# 07_PCIE_WIFI.net
KiCad netlist of a schematic drawn in Altium Designer
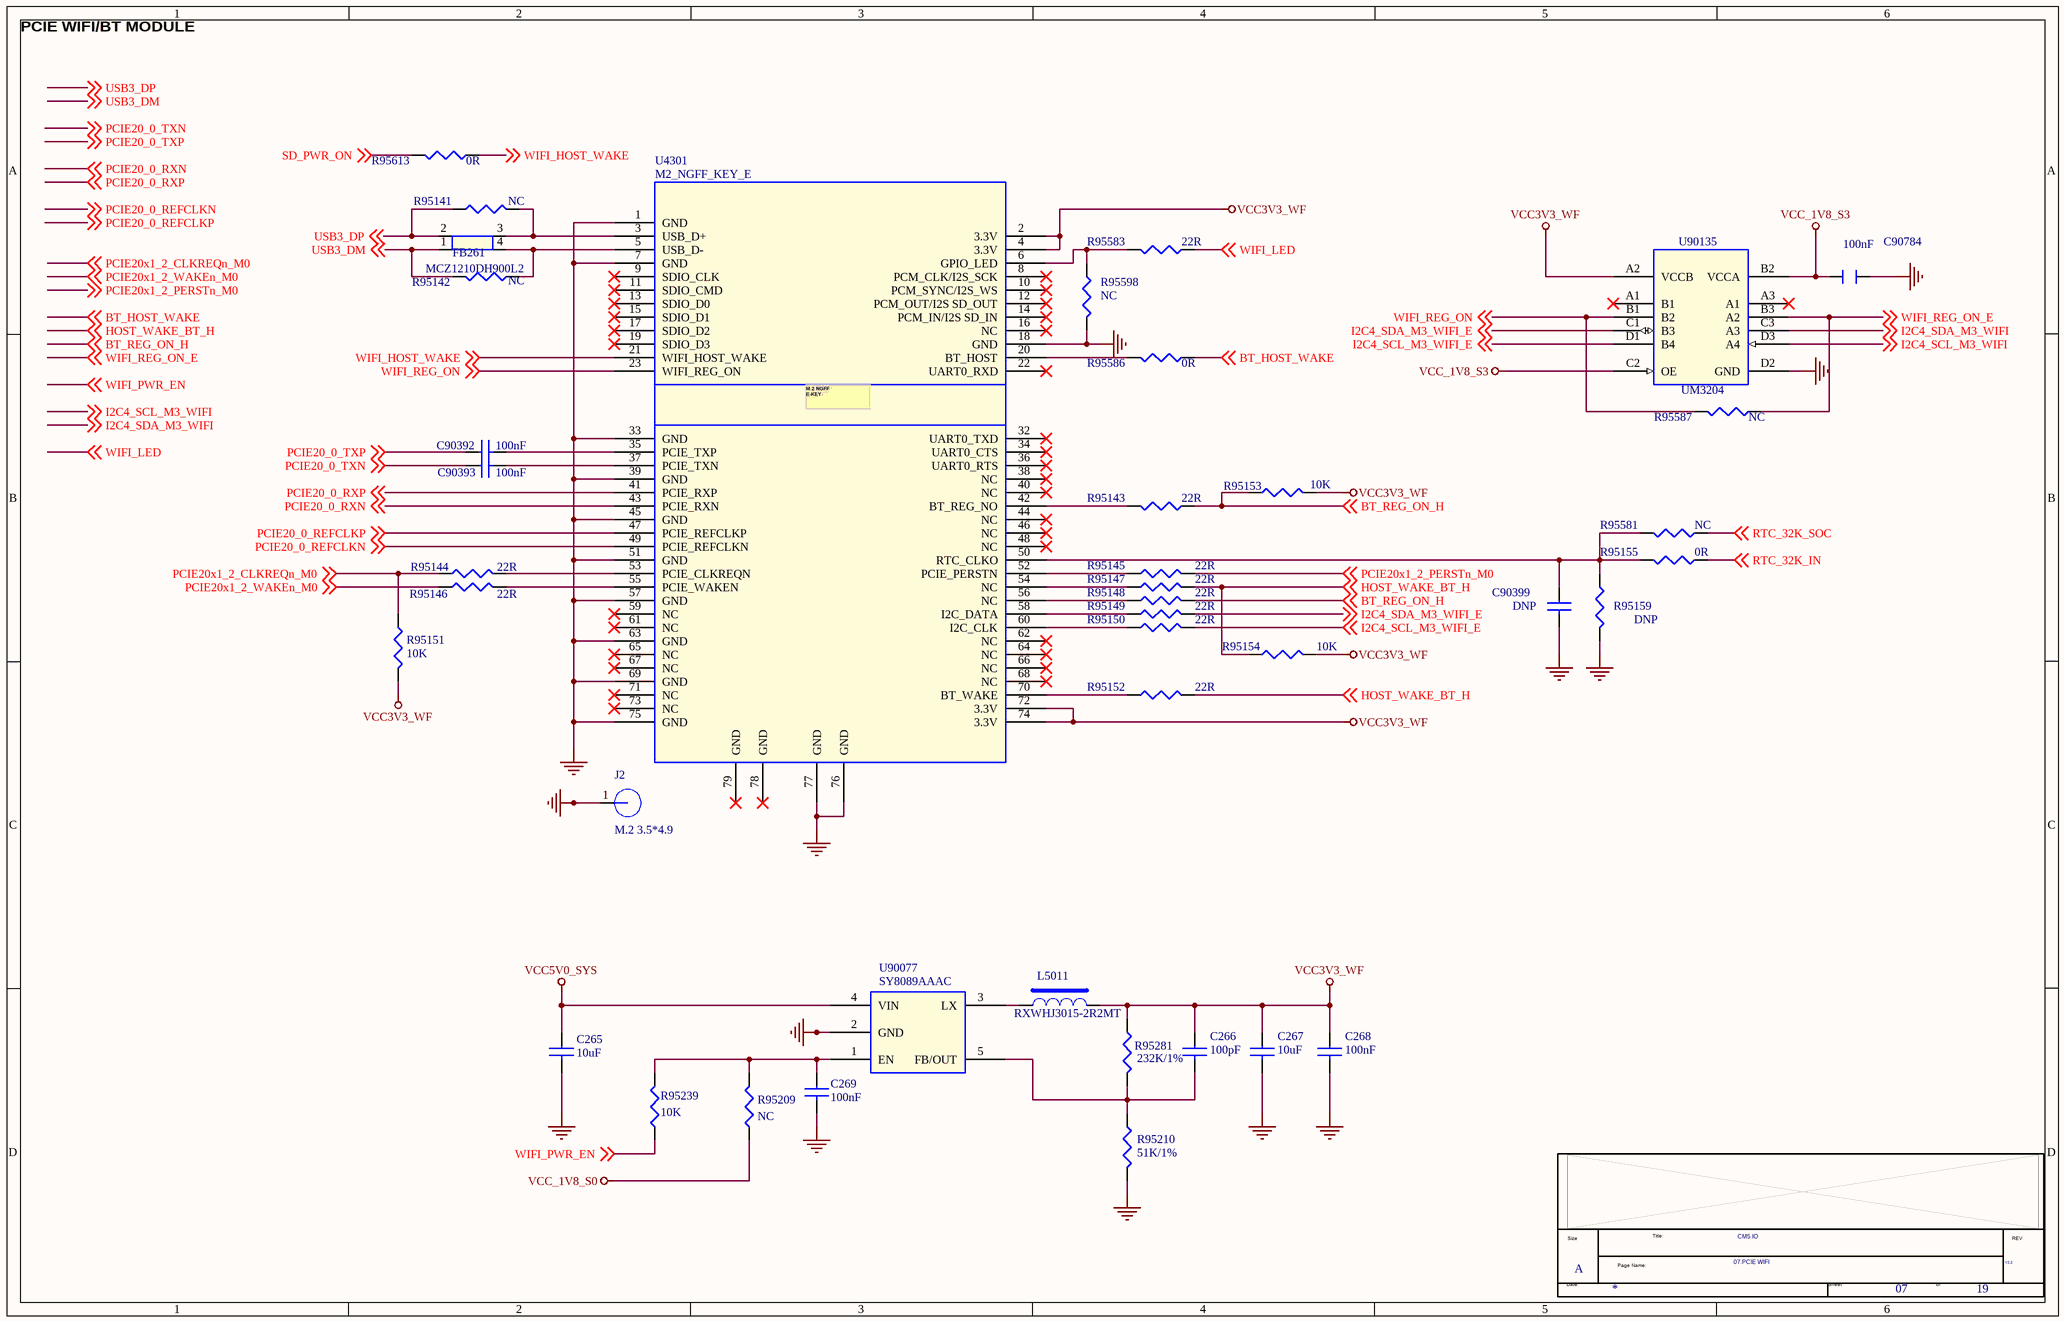
[diagram p0: 07_PCIE_WIFI.SchDoc]

(export (version "E")
  (design (tool "Eeschema 10.0.6"))
  (components
    (comp (ref "*")
      (value "radxa_1010")
      (fields
        (field (name "DOC") "07.PCIE WIFI")
        (field (name "REVCODE") "V2.2")
        (field (name "TITLE") "CM5 IO")
        (field (name "PAGE SIZE") "A")
        (field (name "PAGE NUMBER") "07")
        (field (name "PAGE COUNT") "19")
      )
      (libsource (lib "*") (part "radxa_1010"))
    )
    (comp (ref "C265")
      (value "10uF")
      (footprint "C0603")
      (description "cap,10.00uF,+/-10%,10V,X5R,C0805")
      (fields
        (field (name "VOLTAGE") "6.3V")
        (field (name "TOLERANCE") "10%")
        (field (name "CREATED BY") "JJJ")
      )
      (libsource (lib "*") (part "CAP NP_0_Dup5"))
    )
    (comp (ref "C266")
      (value "100pF")
      (footprint "C0201")
      (description "cap,100.00pF,+/-5%,50V,C0G,C0402")
      (fields
        (field (name "VOLTAGE") "25V")
        (field (name "TOLERANCE") "5%")
        (field (name "CREATED BY") "JJJ")
      )
      (libsource (lib "*") (part "CAP NP_0_Dup5"))
    )
    (comp (ref "C267")
      (value "10uF")
      (footprint "C0603")
      (description "cap,10.00uF,+/-10%,10V,X5R,C0805")
      (fields
        (field (name "VOLTAGE") "6.3V")
        (field (name "TOLERANCE") "10%")
        (field (name "CREATED BY") "JJJ")
      )
      (libsource (lib "*") (part "CAP NP_0_Dup5"))
    )
    (comp (ref "C268")
      (value "100nF")
      (footprint "C0201")
      (description "cap,100.00nF,+/-10%,16V,X5R,C0402")
      (fields
        (field (name "VOLTAGE") "16V")
        (field (name "TOLERANCE") "10%")
        (field (name "CREATED BY") "JJJ")
      )
      (libsource (lib "*") (part "CAP NP_0_Dup5"))
    )
    (comp (ref "C269")
      (value "100nF")
      (footprint "C0201")
      (description "cap,100.00nF,+/-10%,16V,X5R,C0402")
      (fields
        (field (name "VOLTAGE") "16V")
        (field (name "MANUFACTURER") "TDK")
        (field (name "CREATED BY") "JJJ")
      )
      (libsource (lib "*") (part "CAP NP_0_Dup5"))
    )
    (comp (ref "C90392")
      (value "100nF")
      (footprint "C0201")
      (description "cap,100.00nF,+/-10%,10V,X5R,C0201")
      (fields
        (field (name "VOLTAGE") "10V")
        (field (name "TOLERANCE") "10%")
        (field (name "CREATED BY") "JJJ")
      )
      (libsource (lib "*") (part "CAP NP_0_Dup5"))
    )
    (comp (ref "C90393")
      (value "100nF")
      (footprint "C0201")
      (description "cap,100.00nF,+/-10%,10V,X5R,C0201")
      (fields
        (field (name "VOLTAGE") "10V")
        (field (name "MANUFACTURER") "TDK")
        (field (name "CREATED BY") "JJJ")
      )
      (libsource (lib "*") (part "CAP NP_0_Dup5"))
    )
    (comp (ref "C90399")
      (value "DNP")
      (footprint "C0402")
      (description "Did Not Place.")
      (fields (field (name "CREATED BY") "JJJ"))
      (libsource (lib "*") (part "CAP NP_0_Dup5"))
    )
    (comp (ref "C90784") (value "100nF") (footprint "C0402") (libsource (lib "*") (part "CAPACITOR_0")))
    (comp (ref "FB261")
      (value "MCZ1210DH900L2")
      (footprint "MCZ1210AH900L2")
      (libsource (lib "*") (part "MCZ1210AH900L2_1_Dup1"))
    )
    (comp (ref "J2")
      (value "M.2 3.5*4.9")
      (footprint "H3.8MM")
      (description "直径3.5mm hole")
      (fields (field (name "CREATED BY") "CZD"))
      (libsource (lib "*") (part "HOLE"))
    )
    (comp (ref "L5011")
      (value "RXWHJ3015-2R2MT")
      (footprint "IND_303015")
      (description "Power Inductor,2.2uH,0.3,IND_303015")
      (fields
        (field (name "MANUFACTURER") "sunlord")
        (field (name "TOLERANCE") "30%")
        (field (name "CREATED BY") "YTL")
      )
      (libsource (lib "*") (part "INDUCTORS OF FERRITE_Dup1"))
    )
    (comp (ref "R95141")
      (value "NC")
      (footprint "R0402")
      (description "通用厚膜电阻,33R,+/-5%,R0402,1/16W.")
      (fields
        (field (name "TOLERANCE") "5%")
        (field (name "MANUFACTURER") "YAGEO")
        (field (name "CREATED BY") "YTL")
      )
      (libsource (lib "*") (part "RESISTOR_0_Dup2"))
    )
    (comp (ref "R95142")
      (value "NC")
      (footprint "R0402")
      (description "通用厚膜电阻,33R,+/-5%,R0402,1/16W.")
      (fields
        (field (name "TOLERANCE") "5%")
        (field (name "MANUFACTURER") "YAGEO")
        (field (name "CREATED BY") "YTL")
      )
      (libsource (lib "*") (part "RESISTOR_0_Dup2"))
    )
    (comp (ref "R95143")
      (value "22R")
      (footprint "R0402")
      (description "通用厚膜电阻,22R,+/-5%,R0402,1/16W.")
      (fields
        (field (name "TOLERANCE") "5%")
        (field (name "MANUFACTURER") "YAGEO")
        (field (name "CREATED BY") "YTL")
      )
      (libsource (lib "*") (part "RESISTOR_0_Dup2"))
    )
    (comp (ref "R95144")
      (value "22R")
      (footprint "R0402")
      (description "通用厚膜电阻,22R,+/-5%,R0402,1/16W.")
      (fields
        (field (name "TOLERANCE") "5%")
        (field (name "MANUFACTURER") "YAGEO")
        (field (name "CREATED BY") "YTL")
      )
      (libsource (lib "*") (part "RESISTOR_0_Dup2"))
    )
    (comp (ref "R95145")
      (value "22R")
      (footprint "R0402")
      (description "通用厚膜电阻,22R,+/-5%,R0402,1/16W.")
      (fields
        (field (name "TOLERANCE") "5%")
        (field (name "MANUFACTURER") "YAGEO")
        (field (name "CREATED BY") "YTL")
      )
      (libsource (lib "*") (part "RESISTOR_0_Dup2"))
    )
    (comp (ref "R95146")
      (value "22R")
      (footprint "R0402")
      (description "通用厚膜电阻,22R,+/-5%,R0402,1/16W.")
      (fields
        (field (name "TOLERANCE") "5%")
        (field (name "MANUFACTURER") "YAGEO")
        (field (name "CREATED BY") "YTL")
      )
      (libsource (lib "*") (part "RESISTOR_0_Dup2"))
    )
    (comp (ref "R95147")
      (value "22R")
      (footprint "R0402")
      (description "通用厚膜电阻,22R,+/-5%,R0402,1/16W.")
      (fields
        (field (name "TOLERANCE") "5%")
        (field (name "MANUFACTURER") "YAGEO")
        (field (name "CREATED BY") "YTL")
      )
      (libsource (lib "*") (part "RESISTOR_0_Dup2"))
    )
    (comp (ref "R95148")
      (value "22R")
      (footprint "R0402")
      (description "通用厚膜电阻,22R,+/-5%,R0402,1/16W.")
      (fields
        (field (name "TOLERANCE") "5%")
        (field (name "MANUFACTURER") "YAGEO")
        (field (name "CREATED BY") "YTL")
      )
      (libsource (lib "*") (part "RESISTOR_0_Dup2"))
    )
    (comp (ref "R95149")
      (value "22R")
      (footprint "R0402")
      (description "通用厚膜电阻,22R,+/-5%,R0402,1/16W.")
      (fields
        (field (name "TOLERANCE") "5%")
        (field (name "MANUFACTURER") "YAGEO")
        (field (name "CREATED BY") "YTL")
      )
      (libsource (lib "*") (part "RESISTOR_0_Dup2"))
    )
    (comp (ref "R95150")
      (value "22R")
      (footprint "R0402")
      (description "通用厚膜电阻,22R,+/-5%,R0402,1/16W.")
      (fields
        (field (name "TOLERANCE") "5%")
        (field (name "MANUFACTURER") "YAGEO")
        (field (name "CREATED BY") "YTL")
      )
      (libsource (lib "*") (part "RESISTOR_0_Dup2"))
    )
    (comp (ref "R95151")
      (value "10K")
      (footprint "R0402")
      (description "通用厚膜电阻,10K,+/-5%,R0402,1/16W.")
      (fields
        (field (name "TOLERANCE") "5%")
        (field (name "MANUFACTURER") "YAGEO")
        (field (name "CREATED BY") "YTL")
      )
      (libsource (lib "*") (part "RESISTOR_0_Dup2"))
    )
    (comp (ref "R95152")
      (value "22R")
      (footprint "R0402")
      (description "通用厚膜电阻,22R,+/-5%,R0402,1/16W.")
      (fields
        (field (name "TOLERANCE") "5%")
        (field (name "MANUFACTURER") "YAGEO")
        (field (name "CREATED BY") "YTL")
      )
      (libsource (lib "*") (part "RESISTOR_0_Dup2"))
    )
    (comp (ref "R95153")
      (value "10K")
      (footprint "R0402")
      (description "通用厚膜电阻,10K,+/-5%,R0402,1/16W.")
      (fields
        (field (name "TOLERANCE") "5%")
        (field (name "MANUFACTURER") "YAGEO")
        (field (name "CREATED BY") "YTL")
      )
      (libsource (lib "*") (part "RESISTOR_0_Dup2"))
    )
    (comp (ref "R95154")
      (value "10K")
      (footprint "R0402")
      (description "通用厚膜电阻,10K,+/-5%,R0402,1/16W.")
      (fields
        (field (name "TOLERANCE") "5%")
        (field (name "MANUFACTURER") "YAGEO")
        (field (name "CREATED BY") "YTL")
      )
      (libsource (lib "*") (part "RESISTOR_0_Dup2"))
    )
    (comp (ref "R95155")
      (value "0R")
      (footprint "R0402")
      (description "通用厚膜电阻,0R,+/-5%,R0402,1/16W.")
      (fields
        (field (name "TOLERANCE") "5%")
        (field (name "MANUFACTURER") "YAGEO")
        (field (name "CREATED BY") "YTL")
      )
      (libsource (lib "*") (part "RESISTOR_0_Dup2"))
    )
    (comp (ref "R95159")
      (value "DNP")
      (footprint "R0402")
      (description "Did Not Place.")
      (fields (field (name "CREATED BY") "JJJ"))
      (libsource (lib "*") (part "RESISTOR_0_Dup2"))
    )
    (comp (ref "R95209")
      (value "NC")
      (footprint "R0402")
      (description "通用厚膜电阻,10K,+/-5%,R0402,1/16W.")
      (fields
        (field (name "TOLERANCE") "5%")
        (field (name "MANUFACTURER") "YAGEO")
        (field (name "CREATED BY") "YTL")
      )
      (libsource (lib "*") (part "RESISTOR_0_Dup2"))
    )
    (comp (ref "R95210")
      (value "51K/1%")
      (footprint "R0402")
      (description "通用厚膜电阻,47K,+/-1%,R0402,1/16W.")
      (fields
        (field (name "TOLERANCE") "1%")
        (field (name "MANUFACTURER") "YAGEO")
        (field (name "CREATED BY") "YTL")
      )
      (libsource (lib "*") (part "RESISTOR_0_Dup2"))
    )
    (comp (ref "R95239")
      (value "10K")
      (footprint "R0402")
      (description "通用厚膜电阻,10K,+/-5%,R0402,1/16W.")
      (fields
        (field (name "TOLERANCE") "5%")
        (field (name "MANUFACTURER") "YAGEO")
        (field (name "CREATED BY") "YTL")
      )
      (libsource (lib "*") (part "RESISTOR_0_Dup2"))
    )
    (comp (ref "R95281")
      (value "232K/1%")
      (footprint "R0402")
      (description "通用厚膜电阻,200K,+/-1%,R0402,1/16W.")
      (fields
        (field (name "TOLERANCE") "1%")
        (field (name "MANUFACTURER") "YAGEO")
        (field (name "CREATED BY") "YTL")
      )
      (libsource (lib "*") (part "RESISTOR_0_Dup2"))
    )
    (comp (ref "R95581")
      (value "NC")
      (footprint "R0402")
      (description "通用厚膜电阻,0R,+/-5%,R0402,1/16W.")
      (fields
        (field (name "TOLERANCE") "5%")
        (field (name "MANUFACTURER") "YAGEO")
        (field (name "CREATED BY") "YTL")
      )
      (libsource (lib "*") (part "RESISTOR_0_Dup2"))
    )
    (comp (ref "R95583")
      (value "22R")
      (footprint "R0402")
      (description "通用厚膜电阻,22R,+/-5%,R0402,1/16W.")
      (fields
        (field (name "TOLERANCE") "5%")
        (field (name "MANUFACTURER") "YAGEO")
        (field (name "CREATED BY") "YTL")
      )
      (libsource (lib "*") (part "RESISTOR_0_Dup2"))
    )
    (comp (ref "R95586")
      (value "0R")
      (footprint "R0402")
      (description "通用厚膜电阻,22R,+/-5%,R0402,1/16W.")
      (fields
        (field (name "TOLERANCE") "5%")
        (field (name "MANUFACTURER") "YAGEO")
        (field (name "CREATED BY") "YTL")
      )
      (libsource (lib "*") (part "RESISTOR_0_Dup2"))
    )
    (comp (ref "R95587")
      (value "NC")
      (footprint "R0402")
      (description "通用厚膜电阻,22R,+/-5%,R0402,1/16W.")
      (fields
        (field (name "TOLERANCE") "5%")
        (field (name "MANUFACTURER") "YAGEO")
        (field (name "CREATED BY") "YTL")
      )
      (libsource (lib "*") (part "RESISTOR_0_Dup2"))
    )
    (comp (ref "R95598")
      (value "NC")
      (footprint "R0402")
      (description "通用厚膜电阻,22R,+/-5%,R0402,1/16W.")
      (fields
        (field (name "TOLERANCE") "5%")
        (field (name "MANUFACTURER") "YAGEO")
        (field (name "CREATED BY") "YTL")
      )
      (libsource (lib "*") (part "RESISTOR_0_Dup2"))
    )
    (comp (ref "R95613")
      (value "0R")
      (footprint "R0402")
      (description "通用厚膜电阻,22R,+/-5%,R0402,1/16W.")
      (fields
        (field (name "TOLERANCE") "5%")
        (field (name "MANUFACTURER") "YAGEO")
        (field (name "CREATED BY") "YTL")
      )
      (libsource (lib "*") (part "RESISTOR_0_Dup2"))
    )
    (comp (ref "U4301")
      (value "M2_NGFF_KEY_E")
      (footprint "M2_NGFF_KEY_E_1")
      (libsource (lib "*") (part "M_8.2 NGFF EKEY SOCKET"))
    )
    (comp (ref "U90077")
      (value "SY8089AAAC")
      (footprint "SOT_23_5")
      (description "High Efficiency 5.5V, 2A continuous, 3A peak, 1MHz Synchronous Step Down Regulator")
      (fields (field (name "MANUFACTURER") "Silergy（矽力杰）") (field (name "CREATED BY") "JJJ"))
      (libsource (lib "*") (part "DCDC_SY8088"))
    )
    (comp (ref "U90135")
      (value "UM3204")
      (footprint "CSP-12")
      (description "4-bit Bi-directional Level Shifter  UM3204H")
      (fields (field (name "PART NUMBER") "PI4ULS5V104GAEX"))
      (libsource (lib "*") (part "MP2610_0"))
    )
  )
  (nets
    (net (code "1") (name "BT_HOST_WAKE") (class "Default")
      (node (ref "R95586") (pin "1") (pinfunction "1_1") (pintype "passive"))
    )
    (net (code "2") (name "BT_REG_ON_H") (class "Default")
      (node (ref "R95143") (pin "1") (pinfunction "1_1") (pintype "passive"))
      (node (ref "R95148") (pin "1") (pinfunction "1_1") (pintype "passive"))
      (node (ref "R95153") (pin "1") (pinfunction "1_1") (pintype "passive"))
    )
    (net (code "3") (name "GND") (class "Default")
      (node (ref "C265") (pin "2") (pinfunction "2_2") (pintype "passive"))
      (node (ref "C267") (pin "2") (pinfunction "2_2") (pintype "passive"))
      (node (ref "C268") (pin "2") (pinfunction "2_2") (pintype "passive"))
      (node (ref "C269") (pin "2") (pinfunction "2_2") (pintype "passive"))
      (node (ref "C90399") (pin "2") (pinfunction "2_2") (pintype "passive"))
      (node (ref "C90784") (pin "1") (pinfunction "1_1") (pintype "passive"))
      (node (ref "J2") (pin "1") (pinfunction "1_1") (pintype "passive"))
      (node (ref "R95159") (pin "2") (pinfunction "2_2") (pintype "passive"))
      (node (ref "R95210") (pin "2") (pinfunction "2_2") (pintype "passive"))
      (node (ref "R95598") (pin "2") (pinfunction "2_2") (pintype "passive"))
      (node (ref "U4301") (pin "1") (pinfunction "GND_1") (pintype "passive"))
      (node (ref "U4301") (pin "18") (pinfunction "GND_18") (pintype "passive"))
      (node (ref "U4301") (pin "33") (pinfunction "GND_33") (pintype "passive"))
      (node (ref "U4301") (pin "39") (pinfunction "GND_39") (pintype "passive"))
      (node (ref "U4301") (pin "45") (pinfunction "GND_45") (pintype "passive"))
      (node (ref "U4301") (pin "51") (pinfunction "GND_51") (pintype "passive"))
      (node (ref "U4301") (pin "57") (pinfunction "GND_57") (pintype "passive"))
      (node (ref "U4301") (pin "63") (pinfunction "GND_63") (pintype "passive"))
      (node (ref "U4301") (pin "69") (pinfunction "GND_69") (pintype "passive"))
      (node (ref "U4301") (pin "7") (pinfunction "GND_7") (pintype "passive"))
      (node (ref "U4301") (pin "75") (pinfunction "GND_75") (pintype "passive"))
      (node (ref "U4301") (pin "76") (pinfunction "GND_76") (pintype "passive"))
      (node (ref "U4301") (pin "77") (pinfunction "GND_77") (pintype "passive"))
      (node (ref "U90077") (pin "2") (pinfunction "GND_2") (pintype "passive"))
      (node (ref "U90135") (pin "D2") (pinfunction "GND_D2") (pintype "power_in"))
    )
    (net (code "4") (name "HOST_WAKE_BT_H") (class "Default")
      (node (ref "R95147") (pin "1") (pinfunction "1_1") (pintype "passive"))
      (node (ref "R95152") (pin "1") (pinfunction "1_1") (pintype "passive"))
      (node (ref "R95154") (pin "1") (pinfunction "1_1") (pintype "passive"))
    )
    (net (code "5") (name "I2C4_SCL_M3_WIFI") (class "Default")
      (node (ref "U90135") (pin "D3") (pinfunction "A4_D3") (pintype "input"))
    )
    (net (code "6") (name "I2C4_SCL_M3_WIFI_E") (class "Default")
      (node (ref "R95150") (pin "1") (pinfunction "1_1") (pintype "passive"))
      (node (ref "U90135") (pin "D1") (pinfunction "B4_D1") (pintype "tri_state"))
    )
    (net (code "7") (name "I2C4_SDA_M3_WIFI") (class "Default")
      (node (ref "U90135") (pin "C3") (pinfunction "A3_C3") (pintype "tri_state"))
    )
    (net (code "8") (name "I2C4_SDA_M3_WIFI_E") (class "Default")
      (node (ref "R95149") (pin "1") (pinfunction "1_1") (pintype "passive"))
      (node (ref "U90135") (pin "C1") (pinfunction "B3_C1") (pintype "bidirectional"))
    )
    (net (code "9") (name "Net-(R95147-Pad2)") (class "Default")
      (node (ref "R95147") (pin "2") (pinfunction "2_2") (pintype "passive"))
      (node (ref "U4301") (pin "54") (pinfunction "NC_54") (pintype "passive"))
    )
    (net (code "10") (name "Net-(R95148-Pad2)") (class "Default")
      (node (ref "R95148") (pin "2") (pinfunction "2_2") (pintype "passive"))
      (node (ref "U4301") (pin "56") (pinfunction "NC_56") (pintype "passive"))
    )
    (net (code "11") (name "Net-(U4301-BT_HOST)") (class "Default")
      (node (ref "R95586") (pin "2") (pinfunction "2_2") (pintype "passive"))
      (node (ref "U4301") (pin "20") (pinfunction "BT_HOST_20") (pintype "passive"))
    )
    (net (code "12") (name "Net-(U4301-BT_REG_NO)") (class "Default")
      (node (ref "R95143") (pin "2") (pinfunction "2_2") (pintype "passive"))
      (node (ref "U4301") (pin "42") (pinfunction "BT_REG_NO_42") (pintype "passive"))
    )
    (net (code "13") (name "Net-(U4301-BT_WAKE)") (class "Default")
      (node (ref "R95152") (pin "2") (pinfunction "2_2") (pintype "passive"))
      (node (ref "U4301") (pin "70") (pinfunction "BT_WAKE_70") (pintype "passive"))
    )
    (net (code "14") (name "Net-(U4301-GPIO_LED)") (class "Default")
      (node (ref "R95583") (pin "2") (pinfunction "2_2") (pintype "passive"))
      (node (ref "R95598") (pin "1") (pinfunction "1_1") (pintype "passive"))
      (node (ref "U4301") (pin "6") (pinfunction "GPIO_LED_6") (pintype "passive"))
    )
    (net (code "15") (name "Net-(U4301-I2C_CLK)") (class "Default")
      (node (ref "R95150") (pin "2") (pinfunction "2_2") (pintype "passive"))
      (node (ref "U4301") (pin "60") (pinfunction "I2C_CLK_60") (pintype "passive"))
    )
    (net (code "16") (name "Net-(U4301-I2C_DATA)") (class "Default")
      (node (ref "R95149") (pin "2") (pinfunction "2_2") (pintype "passive"))
      (node (ref "U4301") (pin "58") (pinfunction "I2C_DATA_58") (pintype "passive"))
    )
    (net (code "17") (name "Net-(U4301-PCIE_CLKREQN)") (class "Default")
      (node (ref "R95144") (pin "2") (pinfunction "2_2") (pintype "passive"))
      (node (ref "U4301") (pin "53") (pinfunction "PCIE_CLKREQN_53") (pintype "passive"))
    )
    (net (code "18") (name "Net-(U4301-PCIE_PERSTN)") (class "Default")
      (node (ref "R95145") (pin "2") (pinfunction "2_2") (pintype "passive"))
      (node (ref "U4301") (pin "52") (pinfunction "PCIE_PERSTN_52") (pintype "passive"))
    )
    (net (code "19") (name "Net-(U4301-PCIE_TXN)") (class "Default")
      (node (ref "C90393") (pin "2") (pinfunction "2_2") (pintype "passive"))
      (node (ref "U4301") (pin "37") (pinfunction "PCIE_TXN_37") (pintype "passive"))
    )
    (net (code "20") (name "Net-(U4301-PCIE_TXP)") (class "Default")
      (node (ref "C90392") (pin "2") (pinfunction "2_2") (pintype "passive"))
      (node (ref "U4301") (pin "35") (pinfunction "PCIE_TXP_35") (pintype "passive"))
    )
    (net (code "21") (name "Net-(U4301-PCIE_WAKEN)") (class "Default")
      (node (ref "R95146") (pin "2") (pinfunction "2_2") (pintype "passive"))
      (node (ref "U4301") (pin "55") (pinfunction "PCIE_WAKEN_55") (pintype "passive"))
    )
    (net (code "22") (name "Net-(U4301-RTC_CLKO)") (class "Default")
      (node (ref "C90399") (pin "1") (pinfunction "1_1") (pintype "passive"))
      (node (ref "R95155") (pin "2") (pinfunction "2_2") (pintype "passive"))
      (node (ref "R95159") (pin "1") (pinfunction "1_1") (pintype "passive"))
      (node (ref "R95581") (pin "2") (pinfunction "2_2") (pintype "passive"))
      (node (ref "U4301") (pin "50") (pinfunction "RTC_CLKO_50") (pintype "passive"))
    )
    (net (code "23") (name "Net-(U4301-USB_D+)") (class "Default")
      (node (ref "FB261") (pin "3") (pinfunction "3_3") (pintype "passive"))
      (node (ref "R95141") (pin "1") (pinfunction "1_1") (pintype "passive"))
      (node (ref "U4301") (pin "3") (pinfunction "USB_D+_3") (pintype "passive"))
    )
    (net (code "24") (name "Net-(U4301-USB_D-)") (class "Default")
      (node (ref "FB261") (pin "4") (pinfunction "4_4") (pintype "passive"))
      (node (ref "R95142") (pin "1") (pinfunction "1_1") (pintype "passive"))
      (node (ref "U4301") (pin "5") (pinfunction "USB_D-_5") (pintype "passive"))
    )
    (net (code "25") (name "Net-(U90077-EN)") (class "Default")
      (node (ref "C269") (pin "1") (pinfunction "1_1") (pintype "passive"))
      (node (ref "R95209") (pin "2") (pinfunction "2_2") (pintype "passive"))
      (node (ref "R95239") (pin "2") (pinfunction "2_2") (pintype "passive"))
      (node (ref "U90077") (pin "1") (pinfunction "EN_1") (pintype "passive"))
    )
    (net (code "26") (name "Net-(U90077-FB{slash}OUT)") (class "Default")
      (node (ref "C266") (pin "2") (pinfunction "2_2") (pintype "passive"))
      (node (ref "R95210") (pin "1") (pinfunction "1_1") (pintype "passive"))
      (node (ref "R95281") (pin "2") (pinfunction "2_2") (pintype "passive"))
      (node (ref "U90077") (pin "5") (pinfunction "FB/OUT_5") (pintype "passive"))
    )
    (net (code "27") (name "Net-(U90077-LX)") (class "Default")
      (node (ref "L5011") (pin "1") (pinfunction "1_1") (pintype "passive"))
      (node (ref "U90077") (pin "3") (pinfunction "LX_3") (pintype "passive"))
    )
    (net (code "28") (name "PCIE20_0_REFCLKN") (class "Default")
      (node (ref "U4301") (pin "49") (pinfunction "PCIE_REFCLKN_49") (pintype "passive"))
    )
    (net (code "29") (name "PCIE20_0_REFCLKP") (class "Default")
      (node (ref "U4301") (pin "47") (pinfunction "PCIE_REFCLKP_47") (pintype "passive"))
    )
    (net (code "30") (name "PCIE20_0_RXN") (class "Default")
      (node (ref "U4301") (pin "43") (pinfunction "PCIE_RXN_43") (pintype "passive"))
    )
    (net (code "31") (name "PCIE20_0_RXP") (class "Default")
      (node (ref "U4301") (pin "41") (pinfunction "PCIE_RXP_41") (pintype "passive"))
    )
    (net (code "32") (name "PCIE20_0_TXN") (class "Default")
      (node (ref "C90393") (pin "1") (pinfunction "1_1") (pintype "passive"))
    )
    (net (code "33") (name "PCIE20_0_TXP") (class "Default")
      (node (ref "C90392") (pin "1") (pinfunction "1_1") (pintype "passive"))
    )
    (net (code "34") (name "PCIE20x1_2_CLKREQn_M0") (class "Default")
      (node (ref "R95144") (pin "1") (pinfunction "1_1") (pintype "passive"))
      (node (ref "R95151") (pin "1") (pinfunction "1_1") (pintype "passive"))
    )
    (net (code "35") (name "PCIE20x1_2_PERSTn_M0") (class "Default")
      (node (ref "R95145") (pin "1") (pinfunction "1_1") (pintype "passive"))
    )
    (net (code "36") (name "PCIE20x1_2_WAKEn_M0") (class "Default")
      (node (ref "R95146") (pin "1") (pinfunction "1_1") (pintype "passive"))
    )
    (net (code "37") (name "RTC_32K_IN") (class "Default")
      (node (ref "R95155") (pin "1") (pinfunction "1_1") (pintype "passive"))
    )
    (net (code "38") (name "RTC_32K_SOC") (class "Default")
      (node (ref "R95581") (pin "1") (pinfunction "1_1") (pintype "passive"))
    )
    (net (code "39") (name "SD_PWR_ON") (class "Default")
      (node (ref "R95613") (pin "2") (pinfunction "2_2") (pintype "passive"))
    )
    (net (code "40") (name "USB3_DM") (class "Default")
      (node (ref "FB261") (pin "1") (pinfunction "1_1") (pintype "passive"))
      (node (ref "R95142") (pin "2") (pinfunction "2_2") (pintype "passive"))
    )
    (net (code "41") (name "USB3_DP") (class "Default")
      (node (ref "FB261") (pin "2") (pinfunction "2_2") (pintype "passive"))
      (node (ref "R95141") (pin "2") (pinfunction "2_2") (pintype "passive"))
    )
    (net (code "42") (name "VCC3V3_WF") (class "Default")
      (node (ref "C266") (pin "1") (pinfunction "1_1") (pintype "passive"))
      (node (ref "C267") (pin "1") (pinfunction "1_1") (pintype "passive"))
      (node (ref "C268") (pin "1") (pinfunction "1_1") (pintype "passive"))
      (node (ref "L5011") (pin "2") (pinfunction "2_2") (pintype "passive"))
      (node (ref "R95151") (pin "2") (pinfunction "2_2") (pintype "passive"))
      (node (ref "R95153") (pin "2") (pinfunction "2_2") (pintype "passive"))
      (node (ref "R95154") (pin "2") (pinfunction "2_2") (pintype "passive"))
      (node (ref "R95281") (pin "1") (pinfunction "1_1") (pintype "passive"))
      (node (ref "U4301") (pin "2") (pinfunction "3.3V_2") (pintype "passive"))
      (node (ref "U4301") (pin "4") (pinfunction "3.3V_4") (pintype "passive"))
      (node (ref "U4301") (pin "72") (pinfunction "3.3V_72") (pintype "passive"))
      (node (ref "U4301") (pin "74") (pinfunction "3.3V_74") (pintype "passive"))
      (node (ref "U90135") (pin "A2") (pinfunction "VCCB_A2") (pintype "power_in"))
    )
    (net (code "43") (name "VCC5V0_SYS") (class "Default")
      (node (ref "C265") (pin "1") (pinfunction "1_1") (pintype "passive"))
      (node (ref "U90077") (pin "4") (pinfunction "VIN_4") (pintype "passive"))
    )
    (net (code "44") (name "VCC_1V8_S0") (class "Default")
      (node (ref "R95209") (pin "1") (pinfunction "1_1") (pintype "passive"))
    )
    (net (code "45") (name "VCC_1V8_S3") (class "Default")
      (node (ref "C90784") (pin "2") (pinfunction "2_2") (pintype "passive"))
      (node (ref "U90135") (pin "B2") (pinfunction "VCCA_B2") (pintype "power_in"))
      (node (ref "U90135") (pin "C2") (pinfunction "OE_C2") (pintype "input"))
    )
    (net (code "46") (name "WIFI_HOST_WAKE") (class "Default")
      (node (ref "R95613") (pin "1") (pinfunction "1_1") (pintype "passive"))
      (node (ref "U4301") (pin "21") (pinfunction "WIFI_HOST_WAKE_21") (pintype "passive"))
    )
    (net (code "47") (name "WIFI_LED") (class "Default")
      (node (ref "R95583") (pin "1") (pinfunction "1_1") (pintype "passive"))
    )
    (net (code "48") (name "WIFI_PWR_EN") (class "Default")
      (node (ref "R95239") (pin "1") (pinfunction "1_1") (pintype "passive"))
    )
    (net (code "49") (name "WIFI_REG_ON") (class "Default")
      (node (ref "R95587") (pin "2") (pinfunction "2_2") (pintype "passive"))
      (node (ref "U4301") (pin "23") (pinfunction "WIFI_REG_ON_23") (pintype "passive"))
      (node (ref "U90135") (pin "B1") (pinfunction "B2_B1") (pintype "tri_state"))
    )
    (net (code "50") (name "WIFI_REG_ON_E") (class "Default")
      (node (ref "R95587") (pin "1") (pinfunction "1_1") (pintype "passive"))
      (node (ref "U90135") (pin "B3") (pinfunction "A2_B3") (pintype "tri_state"))
    )
    (net (code "51") (name "unconnected-(U4301-GND-Pad78)") (class "Default")
      (node (ref "U4301") (pin "78") (pinfunction "GND_78") (pintype "passive+no_connect"))
    )
    (net (code "52") (name "unconnected-(U4301-GND-Pad79)") (class "Default")
      (node (ref "U4301") (pin "79") (pinfunction "GND_79") (pintype "passive+no_connect"))
    )
    (net (code "53") (name "unconnected-(U4301-NC-Pad16)") (class "Default")
      (node (ref "U4301") (pin "16") (pinfunction "NC_16") (pintype "passive+no_connect"))
    )
    (net (code "54") (name "unconnected-(U4301-NC-Pad38)") (class "Default")
      (node (ref "U4301") (pin "38") (pinfunction "NC_38") (pintype "passive+no_connect"))
    )
    (net (code "55") (name "unconnected-(U4301-NC-Pad40)") (class "Default")
      (node (ref "U4301") (pin "40") (pinfunction "NC_40") (pintype "passive+no_connect"))
    )
    (net (code "56") (name "unconnected-(U4301-NC-Pad44)") (class "Default")
      (node (ref "U4301") (pin "44") (pinfunction "NC_44") (pintype "passive+no_connect"))
    )
    (net (code "57") (name "unconnected-(U4301-NC-Pad46)") (class "Default")
      (node (ref "U4301") (pin "46") (pinfunction "NC_46") (pintype "passive+no_connect"))
    )
    (net (code "58") (name "unconnected-(U4301-NC-Pad48)") (class "Default")
      (node (ref "U4301") (pin "48") (pinfunction "NC_48") (pintype "passive+no_connect"))
    )
    (net (code "59") (name "unconnected-(U4301-NC-Pad59)") (class "Default")
      (node (ref "U4301") (pin "59") (pinfunction "NC_59") (pintype "passive+no_connect"))
    )
    (net (code "60") (name "unconnected-(U4301-NC-Pad61)") (class "Default")
      (node (ref "U4301") (pin "61") (pinfunction "NC_61") (pintype "passive+no_connect"))
    )
    (net (code "61") (name "unconnected-(U4301-NC-Pad62)") (class "Default")
      (node (ref "U4301") (pin "62") (pinfunction "NC_62") (pintype "passive+no_connect"))
    )
    (net (code "62") (name "unconnected-(U4301-NC-Pad64)") (class "Default")
      (node (ref "U4301") (pin "64") (pinfunction "NC_64") (pintype "passive+no_connect"))
    )
    (net (code "63") (name "unconnected-(U4301-NC-Pad65)") (class "Default")
      (node (ref "U4301") (pin "65") (pinfunction "NC_65") (pintype "passive+no_connect"))
    )
    (net (code "64") (name "unconnected-(U4301-NC-Pad66)") (class "Default")
      (node (ref "U4301") (pin "66") (pinfunction "NC_66") (pintype "passive+no_connect"))
    )
    (net (code "65") (name "unconnected-(U4301-NC-Pad67)") (class "Default")
      (node (ref "U4301") (pin "67") (pinfunction "NC_67") (pintype "passive+no_connect"))
    )
    (net (code "66") (name "unconnected-(U4301-NC-Pad68)") (class "Default")
      (node (ref "U4301") (pin "68") (pinfunction "NC_68") (pintype "passive+no_connect"))
    )
    (net (code "67") (name "unconnected-(U4301-NC-Pad71)") (class "Default")
      (node (ref "U4301") (pin "71") (pinfunction "NC_71") (pintype "passive+no_connect"))
    )
    (net (code "68") (name "unconnected-(U4301-NC-Pad73)") (class "Default")
      (node (ref "U4301") (pin "73") (pinfunction "NC_73") (pintype "passive+no_connect"))
    )
    (net (code "69") (name "unconnected-(U4301-PCM_CLK{slash}I2S_SCK-Pad8)") (class "Default")
      (node (ref "U4301") (pin "8") (pinfunction "PCM_CLK/I2S_SCK_8") (pintype "passive+no_connect"))
    )
    (net (code "70") (name "unconnected-(U4301-PCM_IN{slash}I2S_SD_IN-Pad14)") (class "Default")
      (node (ref "U4301") (pin "14") (pinfunction "PCM_IN/I2S_SD_IN_14") (pintype "passive+no_connect"))
    )
    (net (code "71") (name "unconnected-(U4301-PCM_OUT{slash}I2S_SD_OUT-Pad12)") (class "Default")
      (node (ref "U4301") (pin "12") (pinfunction "PCM_OUT/I2S_SD_OUT_12") (pintype "passive+no_connect"))
    )
    (net (code "72") (name "unconnected-(U4301-PCM_SYNC{slash}I2S_WS-Pad10)") (class "Default")
      (node (ref "U4301") (pin "10") (pinfunction "PCM_SYNC/I2S_WS_10") (pintype "passive+no_connect"))
    )
    (net (code "73") (name "unconnected-(U4301-SDIO_CLK-Pad9)") (class "Default")
      (node (ref "U4301") (pin "9") (pinfunction "SDIO_CLK_9") (pintype "passive+no_connect"))
    )
    (net (code "74") (name "unconnected-(U4301-SDIO_CMD-Pad11)") (class "Default")
      (node (ref "U4301") (pin "11") (pinfunction "SDIO_CMD_11") (pintype "passive+no_connect"))
    )
    (net (code "75") (name "unconnected-(U4301-SDIO_D0-Pad13)") (class "Default")
      (node (ref "U4301") (pin "13") (pinfunction "SDIO_D0_13") (pintype "passive+no_connect"))
    )
    (net (code "76") (name "unconnected-(U4301-SDIO_D1-Pad15)") (class "Default")
      (node (ref "U4301") (pin "15") (pinfunction "SDIO_D1_15") (pintype "passive+no_connect"))
    )
    (net (code "77") (name "unconnected-(U4301-SDIO_D2-Pad17)") (class "Default")
      (node (ref "U4301") (pin "17") (pinfunction "SDIO_D2_17") (pintype "passive+no_connect"))
    )
    (net (code "78") (name "unconnected-(U4301-SDIO_D3-Pad19)") (class "Default")
      (node (ref "U4301") (pin "19") (pinfunction "SDIO_D3_19") (pintype "passive+no_connect"))
    )
    (net (code "79") (name "unconnected-(U4301-UART0_CTS-Pad34)") (class "Default")
      (node (ref "U4301") (pin "34") (pinfunction "UART0_CTS_34") (pintype "passive+no_connect"))
    )
    (net (code "80") (name "unconnected-(U4301-UART0_RTS-Pad36)") (class "Default")
      (node (ref "U4301") (pin "36") (pinfunction "UART0_RTS_36") (pintype "passive+no_connect"))
    )
    (net (code "81") (name "unconnected-(U4301-UART0_RXD-Pad22)") (class "Default")
      (node (ref "U4301") (pin "22") (pinfunction "UART0_RXD_22") (pintype "passive+no_connect"))
    )
    (net (code "82") (name "unconnected-(U4301-UART0_TXD-Pad32)") (class "Default")
      (node (ref "U4301") (pin "32") (pinfunction "UART0_TXD_32") (pintype "passive+no_connect"))
    )
    (net (code "83") (name "unconnected-(U90135-A1-PadA3)") (class "Default")
      (node (ref "U90135") (pin "A3") (pinfunction "A1_A3") (pintype "tri_state+no_connect"))
    )
    (net (code "84") (name "unconnected-(U90135-B1-PadA1)") (class "Default")
      (node (ref "U90135") (pin "A1") (pinfunction "B1_A1") (pintype "tri_state+no_connect"))
    )
  )
)
